# inverted_board2.net
KiCad netlist of a schematic drawn in EasyEDA Pro
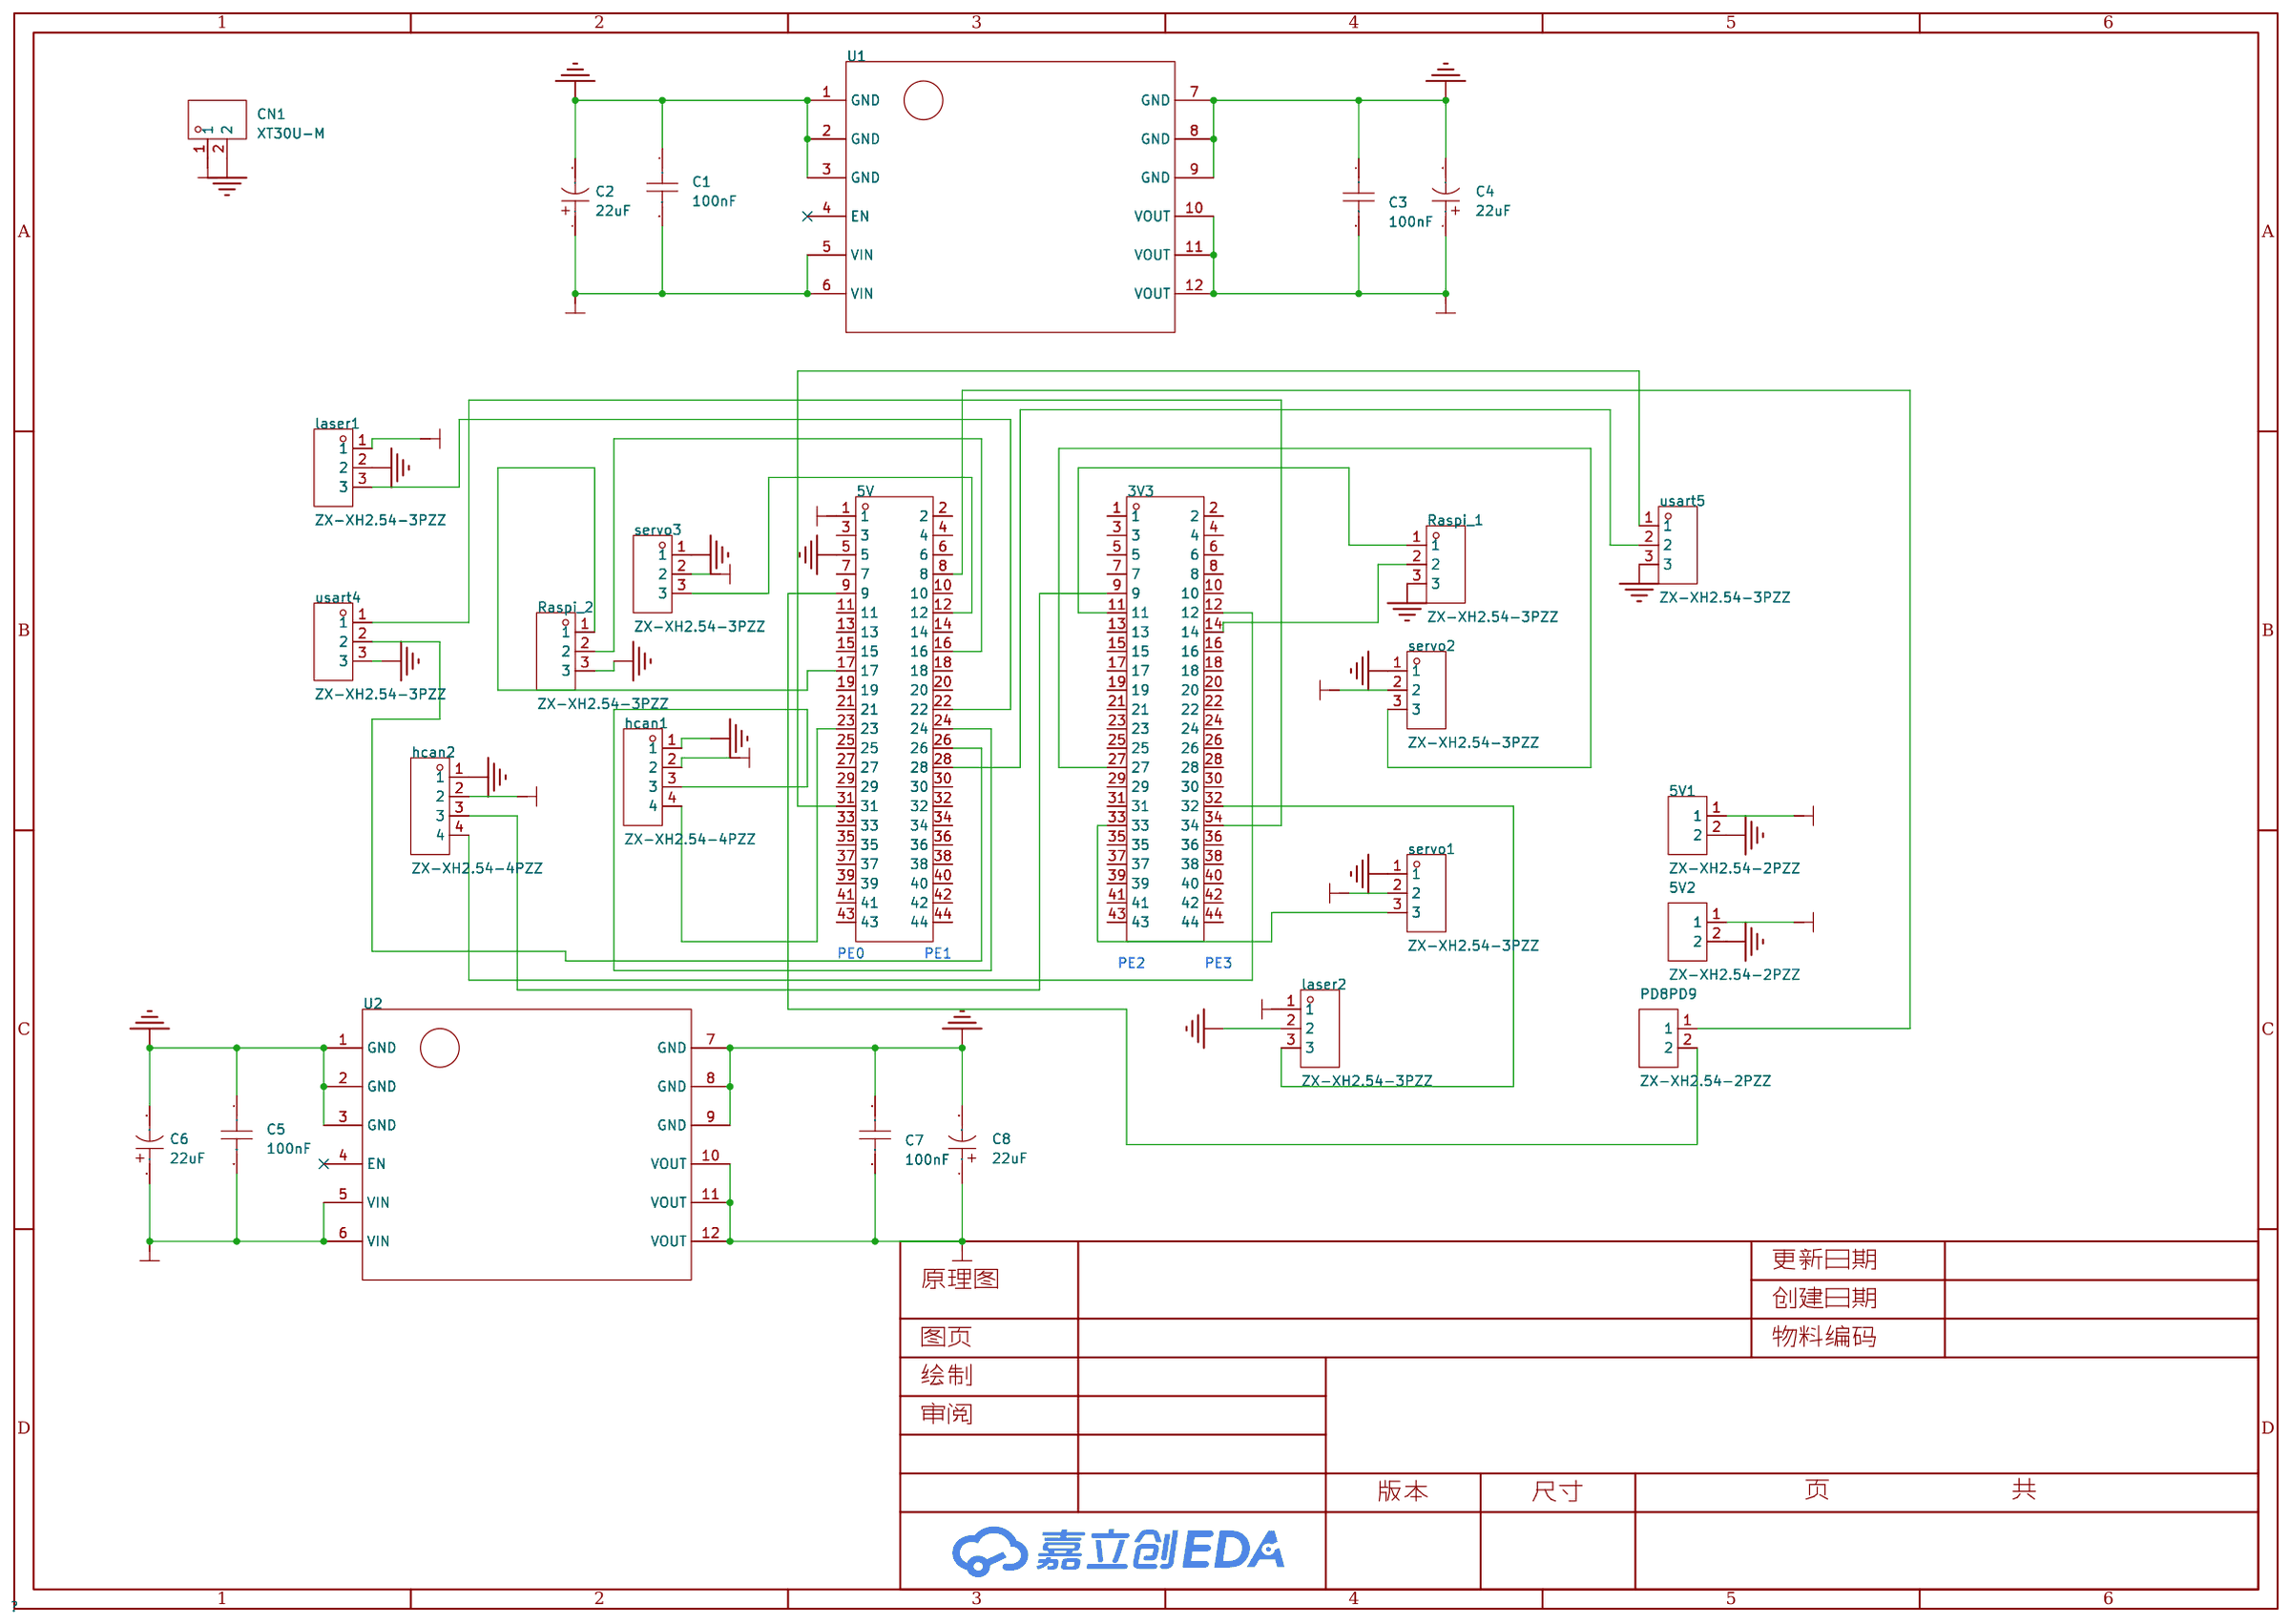
[diagram p0: schematic sheet]

(export (version "E")
  (design (tool "Eeschema 10.0.6"))
  (components
    (comp (ref "3V3")
      (value "X6521FV-2x22-C85D32")
      (footprint "easyedapro:HDR-TH_44P-P2.54-V-F-R2-C22-S2.54")
      (fields (field (name "Manufacturer") "XKB Connection(中国星坤)"))
      (libsource (lib "easyedapro") (part "X6521FV-2X22-C85D32"))
    )
    (comp (ref "5V")
      (value "X6521FV-2x22-C85D32")
      (footprint "easyedapro:HDR-TH_44P-P2.54-V-F-R2-C22-S2.54")
      (fields (field (name "Manufacturer") "XKB Connection(中国星坤)"))
      (libsource (lib "easyedapro") (part "X6521FV-2X22-C85D32"))
    )
    (comp (ref "5V1")
      (value "ZX-XH2.54-2PZZ")
      (footprint "easyedapro:CONN-TH_2P-P2.50_HX25003-2A")
      (fields (field (name "Manufacturer") "Megastar(兆星)"))
      (libsource (lib "easyedapro") (part "ZX-XH2.54-2PZZ"))
    )
    (comp (ref "5V2")
      (value "ZX-XH2.54-2PZZ")
      (footprint "easyedapro:CONN-TH_2P-P2.50_HX25003-2A")
      (fields (field (name "Manufacturer") "Megastar(兆星)"))
      (libsource (lib "easyedapro") (part "ZX-XH2.54-2PZZ"))
    )
    (comp (ref "C1")
      (value "100nF")
      (footprint "easyedapro:C0603")
      (description "容值:100nF;精度:±10%;额定电压:50V;温度系数:X7R;")
      (fields
        (field (name "Manufacturer Part") "CGA0603X7R104K500JT")
        (field (name "Manufacturer") "HRE(芯声)")
      )
      (libsource (lib "easyedapro") (part "CGA0603X7R104K500JT"))
    )
    (comp (ref "C2")
      (value "22uF")
      (footprint "easyedapro:CAP-TH_BD8.0-P5.00-D0.6-FD")
      (description "容值:22uF;额定电压:400V;")
      (fields
        (field (name "Manufacturer Part") "CD110226M2G0816VFL")
        (field (name "Manufacturer") "HRK(鸿瑞凯)")
      )
      (libsource (lib "easyedapro") (part "CD110226M2G0816VFL"))
    )
    (comp (ref "C3")
      (value "100nF")
      (footprint "easyedapro:C0603")
      (description "容值:100nF;精度:±10%;额定电压:50V;温度系数:X7R;")
      (fields
        (field (name "Manufacturer Part") "CGA0603X7R104K500JT")
        (field (name "Manufacturer") "HRE(芯声)")
      )
      (libsource (lib "easyedapro") (part "CGA0603X7R104K500JT"))
    )
    (comp (ref "C4")
      (value "22uF")
      (footprint "easyedapro:CAP-TH_BD8.0-P5.00-D0.6-FD")
      (description "容值:22uF;额定电压:400V;")
      (fields
        (field (name "Manufacturer Part") "CD110226M2G0816VFL")
        (field (name "Manufacturer") "HRK(鸿瑞凯)")
      )
      (libsource (lib "easyedapro") (part "CD110226M2G0816VFL"))
    )
    (comp (ref "C5")
      (value "100nF")
      (footprint "easyedapro:C0603")
      (description "容值:100nF;精度:±10%;额定电压:50V;温度系数:X7R;")
      (fields
        (field (name "Manufacturer Part") "CGA0603X7R104K500JT")
        (field (name "Manufacturer") "HRE(芯声)")
      )
      (libsource (lib "easyedapro") (part "CGA0603X7R104K500JT"))
    )
    (comp (ref "C6")
      (value "22uF")
      (footprint "easyedapro:CAP-TH_BD8.0-P5.00-D0.6-FD")
      (description "容值:22uF;额定电压:400V;")
      (fields
        (field (name "Manufacturer Part") "CD110226M2G0816VFL")
        (field (name "Manufacturer") "HRK(鸿瑞凯)")
      )
      (libsource (lib "easyedapro") (part "CD110226M2G0816VFL"))
    )
    (comp (ref "C7")
      (value "100nF")
      (footprint "easyedapro:C0603")
      (description "容值:100nF;精度:±10%;额定电压:50V;温度系数:X7R;")
      (fields
        (field (name "Manufacturer Part") "CGA0603X7R104K500JT")
        (field (name "Manufacturer") "HRE(芯声)")
      )
      (libsource (lib "easyedapro") (part "CGA0603X7R104K500JT"))
    )
    (comp (ref "C8")
      (value "22uF")
      (footprint "easyedapro:CAP-TH_BD8.0-P5.00-D0.6-FD")
      (description "容值:22uF;额定电压:400V;")
      (fields
        (field (name "Manufacturer Part") "CD110226M2G0816VFL")
        (field (name "Manufacturer") "HRK(鸿瑞凯)")
      )
      (libsource (lib "easyedapro") (part "CD110226M2G0816VFL"))
    )
    (comp (ref "CN1")
      (value "XT30U-M")
      (footprint "easyedapro:CONN-TH_XT30U-M")
      (description "类别:-;类型1:-;")
      (fields (field (name "Manufacturer") "AMASS(艾迈斯)"))
      (libsource (lib "easyedapro") (part "XT30U-M"))
    )
    (comp (ref "hcan1")
      (value "ZX-XH2.54-4PZZ")
      (footprint "easyedapro:CONN-TH_4P-P2.50_4PIN")
      (fields (field (name "Manufacturer") "Megastar(兆星)"))
      (libsource (lib "easyedapro") (part "ZX-XH2.54-4PZZ"))
    )
    (comp (ref "hcan2")
      (value "ZX-XH2.54-4PZZ")
      (footprint "easyedapro:CONN-TH_4P-P2.50_4PIN")
      (fields (field (name "Manufacturer") "Megastar(兆星)"))
      (libsource (lib "easyedapro") (part "ZX-XH2.54-4PZZ"))
    )
    (comp (ref "laser1")
      (value "ZX-XH2.54-3PZZ")
      (footprint "easyedapro:CONN-TH_3P-P2.54_2501S-3P")
      (fields (field (name "Manufacturer") "Megastar(兆星)"))
      (libsource (lib "easyedapro") (part "ZX-XH2.54-3PZZ"))
    )
    (comp (ref "laser2")
      (value "ZX-XH2.54-3PZZ")
      (footprint "easyedapro:CONN-TH_3P-P2.54_2501S-3P")
      (fields (field (name "Manufacturer") "Megastar(兆星)"))
      (libsource (lib "easyedapro") (part "ZX-XH2.54-3PZZ"))
    )
    (comp (ref "PD8PD9")
      (value "ZX-XH2.54-2PZZ")
      (footprint "easyedapro:CONN-TH_2P-P2.50_HX25003-2A")
      (fields (field (name "Manufacturer") "Megastar(兆星)"))
      (libsource (lib "easyedapro") (part "ZX-XH2.54-2PZZ"))
    )
    (comp (ref "Raspi_1")
      (value "ZX-XH2.54-3PZZ")
      (footprint "easyedapro:CONN-TH_3P-P2.54_2501S-3P")
      (fields (field (name "Manufacturer") "Megastar(兆星)"))
      (libsource (lib "easyedapro") (part "ZX-XH2.54-3PZZ"))
    )
    (comp (ref "Raspi_2")
      (value "ZX-XH2.54-3PZZ")
      (footprint "easyedapro:CONN-TH_3P-P2.54_2501S-3P")
      (fields (field (name "Manufacturer") "Megastar(兆星)"))
      (libsource (lib "easyedapro") (part "ZX-XH2.54-3PZZ"))
    )
    (comp (ref "servo1")
      (value "ZX-XH2.54-3PZZ")
      (footprint "easyedapro:CONN-TH_3P-P2.54_2501S-3P")
      (fields (field (name "Manufacturer") "Megastar(兆星)"))
      (libsource (lib "easyedapro") (part "ZX-XH2.54-3PZZ"))
    )
    (comp (ref "servo2")
      (value "ZX-XH2.54-3PZZ")
      (footprint "easyedapro:CONN-TH_3P-P2.54_2501S-3P")
      (fields (field (name "Manufacturer") "Megastar(兆星)"))
      (libsource (lib "easyedapro") (part "ZX-XH2.54-3PZZ"))
    )
    (comp (ref "servo3")
      (value "ZX-XH2.54-3PZZ")
      (footprint "easyedapro:CONN-TH_3P-P2.54_2501S-3P")
      (fields (field (name "Manufacturer") "Megastar(兆星)"))
      (libsource (lib "easyedapro") (part "ZX-XH2.54-3PZZ"))
    )
    (comp (ref "U1")
      (value "~")
      (footprint "easyedapro:TPS5430")
      (libsource (lib "easyedapro") (part "12V-5V"))
    )
    (comp (ref "U2")
      (value "~")
      (footprint "easyedapro:TPS5430")
      (libsource (lib "easyedapro") (part "12V-5V"))
    )
    (comp (ref "usart4")
      (value "ZX-XH2.54-3PZZ")
      (footprint "easyedapro:CONN-TH_3P-P2.54_2501S-3P")
      (fields (field (name "Manufacturer") "Megastar(兆星)"))
      (libsource (lib "easyedapro") (part "ZX-XH2.54-3PZZ"))
    )
    (comp (ref "usart5")
      (value "ZX-XH2.54-3PZZ")
      (footprint "easyedapro:CONN-TH_3P-P2.54_2501S-3P")
      (fields (field (name "Manufacturer") "Megastar(兆星)"))
      (libsource (lib "easyedapro") (part "ZX-XH2.54-3PZZ"))
    )
  )
  (nets
    (net (code "1") (name "GND") (class "Default")
      (node (ref "5V") (pin "5") (pinfunction "5_5") (pintype "unspecified"))
      (node (ref "5V1") (pin "2") (pinfunction "2_2") (pintype "unspecified"))
      (node (ref "5V2") (pin "2") (pinfunction "2_2") (pintype "unspecified"))
      (node (ref "C1") (pin "1") (pinfunction "1_1") (pintype "unspecified"))
      (node (ref "C2") (pin "2") (pinfunction "2_2") (pintype "input"))
      (node (ref "C3") (pin "1") (pinfunction "1_1") (pintype "unspecified"))
      (node (ref "C4") (pin "2") (pinfunction "2_2") (pintype "input"))
      (node (ref "C5") (pin "1") (pinfunction "1_1") (pintype "unspecified"))
      (node (ref "C6") (pin "2") (pinfunction "2_2") (pintype "input"))
      (node (ref "C7") (pin "1") (pinfunction "1_1") (pintype "unspecified"))
      (node (ref "C8") (pin "2") (pinfunction "2_2") (pintype "input"))
      (node (ref "CN1") (pin "2") (pinfunction "2_2") (pintype "unspecified"))
      (node (ref "Raspi_1") (pin "3") (pinfunction "3_3") (pintype "unspecified"))
      (node (ref "Raspi_2") (pin "3") (pinfunction "3_3") (pintype "unspecified"))
      (node (ref "U1") (pin "1") (pinfunction "GND_1") (pintype "input"))
      (node (ref "U1") (pin "2") (pinfunction "GND_2") (pintype "input"))
      (node (ref "U1") (pin "3") (pinfunction "GND_3") (pintype "input"))
      (node (ref "U1") (pin "7") (pinfunction "GND_7") (pintype "input"))
      (node (ref "U1") (pin "8") (pinfunction "GND_8") (pintype "input"))
      (node (ref "U1") (pin "9") (pinfunction "GND_9") (pintype "input"))
      (node (ref "U2") (pin "1") (pinfunction "GND_1") (pintype "input"))
      (node (ref "U2") (pin "2") (pinfunction "GND_2") (pintype "input"))
      (node (ref "U2") (pin "3") (pinfunction "GND_3") (pintype "input"))
      (node (ref "U2") (pin "7") (pinfunction "GND_7") (pintype "input"))
      (node (ref "U2") (pin "8") (pinfunction "GND_8") (pintype "input"))
      (node (ref "U2") (pin "9") (pinfunction "GND_9") (pintype "input"))
      (node (ref "hcan1") (pin "1") (pinfunction "1_1") (pintype "unspecified"))
      (node (ref "hcan2") (pin "1") (pinfunction "1_1") (pintype "unspecified"))
      (node (ref "laser1") (pin "2") (pinfunction "2_2") (pintype "unspecified"))
      (node (ref "laser2") (pin "2") (pinfunction "2_2") (pintype "unspecified"))
      (node (ref "servo1") (pin "1") (pinfunction "1_1") (pintype "unspecified"))
      (node (ref "servo2") (pin "1") (pinfunction "1_1") (pintype "unspecified"))
      (node (ref "servo3") (pin "1") (pinfunction "1_1") (pintype "unspecified"))
      (node (ref "usart4") (pin "3") (pinfunction "3_3") (pintype "unspecified"))
      (node (ref "usart5") (pin "3") (pinfunction "3_3") (pintype "unspecified"))
    )
    (net (code "2") (name "Net-(3V3-Pad9)") (class "Default")
      (node (ref "3V3") (pin "9") (pinfunction "9_9") (pintype "unspecified"))
      (node (ref "hcan2") (pin "3") (pinfunction "3_3") (pintype "unspecified"))
    )
    (net (code "3") (name "Net-(3V3-Pad11)") (class "Default")
      (node (ref "3V3") (pin "11") (pinfunction "11_11") (pintype "unspecified"))
      (node (ref "Raspi_1") (pin "1") (pinfunction "1_1") (pintype "unspecified"))
    )
    (net (code "4") (name "Net-(3V3-Pad12)") (class "Default")
      (node (ref "3V3") (pin "12") (pinfunction "12_12") (pintype "unspecified"))
      (node (ref "hcan2") (pin "4") (pinfunction "4_4") (pintype "unspecified"))
    )
    (net (code "5") (name "Net-(3V3-Pad14)") (class "Default")
      (node (ref "3V3") (pin "14") (pinfunction "14_14") (pintype "unspecified"))
      (node (ref "Raspi_1") (pin "2") (pinfunction "2_2") (pintype "unspecified"))
    )
    (net (code "6") (name "Net-(3V3-Pad27)") (class "Default")
      (node (ref "3V3") (pin "27") (pinfunction "27_27") (pintype "unspecified"))
      (node (ref "servo2") (pin "3") (pinfunction "3_3") (pintype "unspecified"))
    )
    (net (code "7") (name "Net-(3V3-Pad32)") (class "Default")
      (node (ref "3V3") (pin "32") (pinfunction "32_32") (pintype "unspecified"))
      (node (ref "laser2") (pin "3") (pinfunction "3_3") (pintype "unspecified"))
    )
    (net (code "8") (name "Net-(3V3-Pad33)") (class "Default")
      (node (ref "3V3") (pin "33") (pinfunction "33_33") (pintype "unspecified"))
      (node (ref "servo1") (pin "3") (pinfunction "3_3") (pintype "unspecified"))
    )
    (net (code "9") (name "Net-(3V3-Pad34)") (class "Default")
      (node (ref "3V3") (pin "34") (pinfunction "34_34") (pintype "unspecified"))
      (node (ref "usart4") (pin "1") (pinfunction "1_1") (pintype "unspecified"))
    )
    (net (code "10") (name "Net-(5V-Pad8)") (class "Default")
      (node (ref "5V") (pin "8") (pinfunction "8_8") (pintype "unspecified"))
      (node (ref "PD8PD9") (pin "1") (pinfunction "1_1") (pintype "unspecified"))
    )
    (net (code "11") (name "Net-(5V-Pad9)") (class "Default")
      (node (ref "5V") (pin "9") (pinfunction "9_9") (pintype "unspecified"))
      (node (ref "PD8PD9") (pin "2") (pinfunction "2_2") (pintype "unspecified"))
    )
    (net (code "12") (name "Net-(5V-Pad12)") (class "Default")
      (node (ref "5V") (pin "12") (pinfunction "12_12") (pintype "unspecified"))
      (node (ref "servo3") (pin "3") (pinfunction "3_3") (pintype "unspecified"))
    )
    (net (code "13") (name "Net-(5V-Pad16)") (class "Default")
      (node (ref "5V") (pin "16") (pinfunction "16_16") (pintype "unspecified"))
      (node (ref "Raspi_2") (pin "2") (pinfunction "2_2") (pintype "unspecified"))
    )
    (net (code "14") (name "Net-(5V-Pad17)") (class "Default")
      (node (ref "5V") (pin "17") (pinfunction "17_17") (pintype "unspecified"))
      (node (ref "Raspi_2") (pin "1") (pinfunction "1_1") (pintype "unspecified"))
    )
    (net (code "15") (name "Net-(5V-Pad22)") (class "Default")
      (node (ref "5V") (pin "22") (pinfunction "22_22") (pintype "unspecified"))
      (node (ref "laser1") (pin "3") (pinfunction "3_3") (pintype "unspecified"))
    )
    (net (code "16") (name "Net-(5V-Pad23)") (class "Default")
      (node (ref "5V") (pin "23") (pinfunction "23_23") (pintype "unspecified"))
      (node (ref "hcan1") (pin "4") (pinfunction "4_4") (pintype "unspecified"))
    )
    (net (code "17") (name "Net-(5V-Pad24)") (class "Default")
      (node (ref "5V") (pin "24") (pinfunction "24_24") (pintype "unspecified"))
      (node (ref "hcan1") (pin "3") (pinfunction "3_3") (pintype "unspecified"))
    )
    (net (code "18") (name "Net-(5V-Pad26)") (class "Default")
      (node (ref "5V") (pin "26") (pinfunction "26_26") (pintype "unspecified"))
      (node (ref "usart4") (pin "2") (pinfunction "2_2") (pintype "unspecified"))
    )
    (net (code "19") (name "Net-(5V-Pad28)") (class "Default")
      (node (ref "5V") (pin "28") (pinfunction "28_28") (pintype "unspecified"))
      (node (ref "usart5") (pin "2") (pinfunction "2_2") (pintype "unspecified"))
    )
    (net (code "20") (name "Net-(5V-Pad31)") (class "Default")
      (node (ref "5V") (pin "31") (pinfunction "31_31") (pintype "unspecified"))
      (node (ref "usart5") (pin "1") (pinfunction "1_1") (pintype "unspecified"))
    )
    (net (code "21") (name "VIN") (class "Default")
      (node (ref "C1") (pin "2") (pinfunction "2_2") (pintype "unspecified"))
      (node (ref "C2") (pin "1") (pinfunction "1_1") (pintype "input"))
      (node (ref "C5") (pin "2") (pinfunction "2_2") (pintype "unspecified"))
      (node (ref "C6") (pin "1") (pinfunction "1_1") (pintype "input"))
      (node (ref "CN1") (pin "1") (pinfunction "1_1") (pintype "unspecified"))
      (node (ref "U1") (pin "5") (pinfunction "VIN_5") (pintype "input"))
      (node (ref "U1") (pin "6") (pinfunction "VIN_6") (pintype "input"))
      (node (ref "U2") (pin "5") (pinfunction "VIN_5") (pintype "input"))
      (node (ref "U2") (pin "6") (pinfunction "VIN_6") (pintype "input"))
    )
    (net (code "22") (name "VOUT_H") (class "Default")
      (node (ref "C3") (pin "2") (pinfunction "2_2") (pintype "unspecified"))
      (node (ref "C4") (pin "1") (pinfunction "1_1") (pintype "input"))
      (node (ref "U1") (pin "10") (pinfunction "VOUT_10") (pintype "input"))
      (node (ref "U1") (pin "11") (pinfunction "VOUT_11") (pintype "input"))
      (node (ref "U1") (pin "12") (pinfunction "VOUT_12") (pintype "input"))
      (node (ref "servo1") (pin "2") (pinfunction "2_2") (pintype "unspecified"))
      (node (ref "servo2") (pin "2") (pinfunction "2_2") (pintype "unspecified"))
      (node (ref "servo3") (pin "2") (pinfunction "2_2") (pintype "unspecified"))
    )
    (net (code "23") (name "VOUT_L") (class "Default")
      (node (ref "5V") (pin "1") (pinfunction "1_1") (pintype "unspecified"))
      (node (ref "5V1") (pin "1") (pinfunction "1_1") (pintype "unspecified"))
      (node (ref "5V2") (pin "1") (pinfunction "1_1") (pintype "unspecified"))
      (node (ref "C7") (pin "2") (pinfunction "2_2") (pintype "unspecified"))
      (node (ref "C8") (pin "1") (pinfunction "1_1") (pintype "input"))
      (node (ref "U2") (pin "10") (pinfunction "VOUT_10") (pintype "input"))
      (node (ref "U2") (pin "11") (pinfunction "VOUT_11") (pintype "input"))
      (node (ref "U2") (pin "12") (pinfunction "VOUT_12") (pintype "input"))
      (node (ref "hcan1") (pin "2") (pinfunction "2_2") (pintype "unspecified"))
      (node (ref "hcan2") (pin "2") (pinfunction "2_2") (pintype "unspecified"))
      (node (ref "laser1") (pin "1") (pinfunction "1_1") (pintype "unspecified"))
      (node (ref "laser2") (pin "1") (pinfunction "1_1") (pintype "unspecified"))
    )
    (net (code "24") (name "unconnected-(3V3-Pad1)") (class "Default")
      (node (ref "3V3") (pin "1") (pinfunction "1_1") (pintype "unspecified"))
    )
    (net (code "25") (name "unconnected-(3V3-Pad2)") (class "Default")
      (node (ref "3V3") (pin "2") (pinfunction "2_2") (pintype "unspecified"))
    )
    (net (code "26") (name "unconnected-(3V3-Pad3)") (class "Default")
      (node (ref "3V3") (pin "3") (pinfunction "3_3") (pintype "unspecified"))
    )
    (net (code "27") (name "unconnected-(3V3-Pad4)") (class "Default")
      (node (ref "3V3") (pin "4") (pinfunction "4_4") (pintype "unspecified"))
    )
    (net (code "28") (name "unconnected-(3V3-Pad5)") (class "Default")
      (node (ref "3V3") (pin "5") (pinfunction "5_5") (pintype "unspecified"))
    )
    (net (code "29") (name "unconnected-(3V3-Pad6)") (class "Default")
      (node (ref "3V3") (pin "6") (pinfunction "6_6") (pintype "unspecified"))
    )
    (net (code "30") (name "unconnected-(3V3-Pad7)") (class "Default")
      (node (ref "3V3") (pin "7") (pinfunction "7_7") (pintype "unspecified"))
    )
    (net (code "31") (name "unconnected-(3V3-Pad8)") (class "Default")
      (node (ref "3V3") (pin "8") (pinfunction "8_8") (pintype "unspecified"))
    )
    (net (code "32") (name "unconnected-(3V3-Pad10)") (class "Default")
      (node (ref "3V3") (pin "10") (pinfunction "10_10") (pintype "unspecified"))
    )
    (net (code "33") (name "unconnected-(3V3-Pad13)") (class "Default")
      (node (ref "3V3") (pin "13") (pinfunction "13_13") (pintype "unspecified"))
    )
    (net (code "34") (name "unconnected-(3V3-Pad15)") (class "Default")
      (node (ref "3V3") (pin "15") (pinfunction "15_15") (pintype "unspecified"))
    )
    (net (code "35") (name "unconnected-(3V3-Pad16)") (class "Default")
      (node (ref "3V3") (pin "16") (pinfunction "16_16") (pintype "unspecified"))
    )
    (net (code "36") (name "unconnected-(3V3-Pad17)") (class "Default")
      (node (ref "3V3") (pin "17") (pinfunction "17_17") (pintype "unspecified"))
    )
    (net (code "37") (name "unconnected-(3V3-Pad18)") (class "Default")
      (node (ref "3V3") (pin "18") (pinfunction "18_18") (pintype "unspecified"))
    )
    (net (code "38") (name "unconnected-(3V3-Pad19)") (class "Default")
      (node (ref "3V3") (pin "19") (pinfunction "19_19") (pintype "unspecified"))
    )
    (net (code "39") (name "unconnected-(3V3-Pad20)") (class "Default")
      (node (ref "3V3") (pin "20") (pinfunction "20_20") (pintype "unspecified"))
    )
    (net (code "40") (name "unconnected-(3V3-Pad21)") (class "Default")
      (node (ref "3V3") (pin "21") (pinfunction "21_21") (pintype "unspecified"))
    )
    (net (code "41") (name "unconnected-(3V3-Pad22)") (class "Default")
      (node (ref "3V3") (pin "22") (pinfunction "22_22") (pintype "unspecified"))
    )
    (net (code "42") (name "unconnected-(3V3-Pad23)") (class "Default")
      (node (ref "3V3") (pin "23") (pinfunction "23_23") (pintype "unspecified"))
    )
    (net (code "43") (name "unconnected-(3V3-Pad24)") (class "Default")
      (node (ref "3V3") (pin "24") (pinfunction "24_24") (pintype "unspecified"))
    )
    (net (code "44") (name "unconnected-(3V3-Pad25)") (class "Default")
      (node (ref "3V3") (pin "25") (pinfunction "25_25") (pintype "unspecified"))
    )
    (net (code "45") (name "unconnected-(3V3-Pad26)") (class "Default")
      (node (ref "3V3") (pin "26") (pinfunction "26_26") (pintype "unspecified"))
    )
    (net (code "46") (name "unconnected-(3V3-Pad28)") (class "Default")
      (node (ref "3V3") (pin "28") (pinfunction "28_28") (pintype "unspecified"))
    )
    (net (code "47") (name "unconnected-(3V3-Pad29)") (class "Default")
      (node (ref "3V3") (pin "29") (pinfunction "29_29") (pintype "unspecified"))
    )
    (net (code "48") (name "unconnected-(3V3-Pad30)") (class "Default")
      (node (ref "3V3") (pin "30") (pinfunction "30_30") (pintype "unspecified"))
    )
    (net (code "49") (name "unconnected-(3V3-Pad31)") (class "Default")
      (node (ref "3V3") (pin "31") (pinfunction "31_31") (pintype "unspecified"))
    )
    (net (code "50") (name "unconnected-(3V3-Pad35)") (class "Default")
      (node (ref "3V3") (pin "35") (pinfunction "35_35") (pintype "unspecified"))
    )
    (net (code "51") (name "unconnected-(3V3-Pad36)") (class "Default")
      (node (ref "3V3") (pin "36") (pinfunction "36_36") (pintype "unspecified"))
    )
    (net (code "52") (name "unconnected-(3V3-Pad37)") (class "Default")
      (node (ref "3V3") (pin "37") (pinfunction "37_37") (pintype "unspecified"))
    )
    (net (code "53") (name "unconnected-(3V3-Pad38)") (class "Default")
      (node (ref "3V3") (pin "38") (pinfunction "38_38") (pintype "unspecified"))
    )
    (net (code "54") (name "unconnected-(3V3-Pad39)") (class "Default")
      (node (ref "3V3") (pin "39") (pinfunction "39_39") (pintype "unspecified"))
    )
    (net (code "55") (name "unconnected-(3V3-Pad40)") (class "Default")
      (node (ref "3V3") (pin "40") (pinfunction "40_40") (pintype "unspecified"))
    )
    (net (code "56") (name "unconnected-(3V3-Pad41)") (class "Default")
      (node (ref "3V3") (pin "41") (pinfunction "41_41") (pintype "unspecified"))
    )
    (net (code "57") (name "unconnected-(3V3-Pad42)") (class "Default")
      (node (ref "3V3") (pin "42") (pinfunction "42_42") (pintype "unspecified"))
    )
    (net (code "58") (name "unconnected-(3V3-Pad43)") (class "Default")
      (node (ref "3V3") (pin "43") (pinfunction "43_43") (pintype "unspecified"))
    )
    (net (code "59") (name "unconnected-(3V3-Pad44)") (class "Default")
      (node (ref "3V3") (pin "44") (pinfunction "44_44") (pintype "unspecified"))
    )
    (net (code "60") (name "unconnected-(5V-Pad2)") (class "Default")
      (node (ref "5V") (pin "2") (pinfunction "2_2") (pintype "unspecified"))
    )
    (net (code "61") (name "unconnected-(5V-Pad3)") (class "Default")
      (node (ref "5V") (pin "3") (pinfunction "3_3") (pintype "unspecified"))
    )
    (net (code "62") (name "unconnected-(5V-Pad4)") (class "Default")
      (node (ref "5V") (pin "4") (pinfunction "4_4") (pintype "unspecified"))
    )
    (net (code "63") (name "unconnected-(5V-Pad6)") (class "Default")
      (node (ref "5V") (pin "6") (pinfunction "6_6") (pintype "unspecified"))
    )
    (net (code "64") (name "unconnected-(5V-Pad7)") (class "Default")
      (node (ref "5V") (pin "7") (pinfunction "7_7") (pintype "unspecified"))
    )
    (net (code "65") (name "unconnected-(5V-Pad10)") (class "Default")
      (node (ref "5V") (pin "10") (pinfunction "10_10") (pintype "unspecified"))
    )
    (net (code "66") (name "unconnected-(5V-Pad11)") (class "Default")
      (node (ref "5V") (pin "11") (pinfunction "11_11") (pintype "unspecified"))
    )
    (net (code "67") (name "unconnected-(5V-Pad13)") (class "Default")
      (node (ref "5V") (pin "13") (pinfunction "13_13") (pintype "unspecified"))
    )
    (net (code "68") (name "unconnected-(5V-Pad14)") (class "Default")
      (node (ref "5V") (pin "14") (pinfunction "14_14") (pintype "unspecified"))
    )
    (net (code "69") (name "unconnected-(5V-Pad15)") (class "Default")
      (node (ref "5V") (pin "15") (pinfunction "15_15") (pintype "unspecified"))
    )
    (net (code "70") (name "unconnected-(5V-Pad18)") (class "Default")
      (node (ref "5V") (pin "18") (pinfunction "18_18") (pintype "unspecified"))
    )
    (net (code "71") (name "unconnected-(5V-Pad19)") (class "Default")
      (node (ref "5V") (pin "19") (pinfunction "19_19") (pintype "unspecified"))
    )
    (net (code "72") (name "unconnected-(5V-Pad20)") (class "Default")
      (node (ref "5V") (pin "20") (pinfunction "20_20") (pintype "unspecified"))
    )
    (net (code "73") (name "unconnected-(5V-Pad21)") (class "Default")
      (node (ref "5V") (pin "21") (pinfunction "21_21") (pintype "unspecified"))
    )
    (net (code "74") (name "unconnected-(5V-Pad25)") (class "Default")
      (node (ref "5V") (pin "25") (pinfunction "25_25") (pintype "unspecified"))
    )
    (net (code "75") (name "unconnected-(5V-Pad27)") (class "Default")
      (node (ref "5V") (pin "27") (pinfunction "27_27") (pintype "unspecified"))
    )
    (net (code "76") (name "unconnected-(5V-Pad29)") (class "Default")
      (node (ref "5V") (pin "29") (pinfunction "29_29") (pintype "unspecified"))
    )
    (net (code "77") (name "unconnected-(5V-Pad30)") (class "Default")
      (node (ref "5V") (pin "30") (pinfunction "30_30") (pintype "unspecified"))
    )
    (net (code "78") (name "unconnected-(5V-Pad32)") (class "Default")
      (node (ref "5V") (pin "32") (pinfunction "32_32") (pintype "unspecified"))
    )
    (net (code "79") (name "unconnected-(5V-Pad33)") (class "Default")
      (node (ref "5V") (pin "33") (pinfunction "33_33") (pintype "unspecified"))
    )
    (net (code "80") (name "unconnected-(5V-Pad34)") (class "Default")
      (node (ref "5V") (pin "34") (pinfunction "34_34") (pintype "unspecified"))
    )
    (net (code "81") (name "unconnected-(5V-Pad35)") (class "Default")
      (node (ref "5V") (pin "35") (pinfunction "35_35") (pintype "unspecified"))
    )
    (net (code "82") (name "unconnected-(5V-Pad36)") (class "Default")
      (node (ref "5V") (pin "36") (pinfunction "36_36") (pintype "unspecified"))
    )
    (net (code "83") (name "unconnected-(5V-Pad37)") (class "Default")
      (node (ref "5V") (pin "37") (pinfunction "37_37") (pintype "unspecified"))
    )
    (net (code "84") (name "unconnected-(5V-Pad38)") (class "Default")
      (node (ref "5V") (pin "38") (pinfunction "38_38") (pintype "unspecified"))
    )
    (net (code "85") (name "unconnected-(5V-Pad39)") (class "Default")
      (node (ref "5V") (pin "39") (pinfunction "39_39") (pintype "unspecified"))
    )
    (net (code "86") (name "unconnected-(5V-Pad40)") (class "Default")
      (node (ref "5V") (pin "40") (pinfunction "40_40") (pintype "unspecified"))
    )
    (net (code "87") (name "unconnected-(5V-Pad41)") (class "Default")
      (node (ref "5V") (pin "41") (pinfunction "41_41") (pintype "unspecified"))
    )
    (net (code "88") (name "unconnected-(5V-Pad42)") (class "Default")
      (node (ref "5V") (pin "42") (pinfunction "42_42") (pintype "unspecified"))
    )
    (net (code "89") (name "unconnected-(5V-Pad43)") (class "Default")
      (node (ref "5V") (pin "43") (pinfunction "43_43") (pintype "unspecified"))
    )
    (net (code "90") (name "unconnected-(5V-Pad44)") (class "Default")
      (node (ref "5V") (pin "44") (pinfunction "44_44") (pintype "unspecified"))
    )
    (net (code "91") (name "unconnected-(U1-EN-Pad4)") (class "Default")
      (node (ref "U1") (pin "4") (pinfunction "EN_4") (pintype "input+no_connect"))
    )
    (net (code "92") (name "unconnected-(U2-EN-Pad4)") (class "Default")
      (node (ref "U2") (pin "4") (pinfunction "EN_4") (pintype "input+no_connect"))
    )
  )
)
